# LSM6DSMTR.net
KiCad netlist of a schematic drawn in Altium Designer
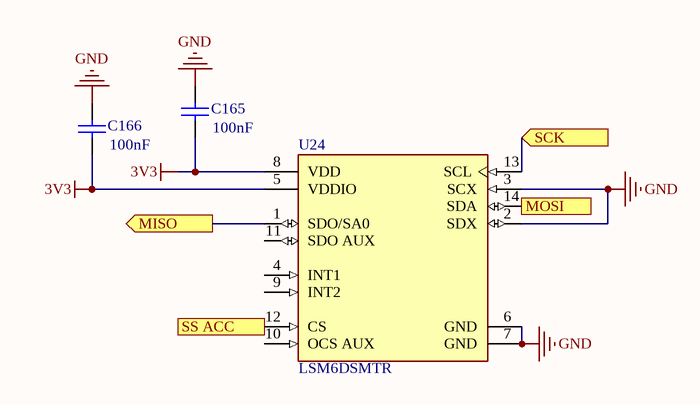
[diagram p0: LSM6DSMTR.SchDoc]

(export (version "E")
  (design (tool "Eeschema 10.0.6"))
  (components
    (comp (ref "C165")
      (value "100nF")
      (footprint "1608[0603]")
      (description "Capacitor")
      (fields (field (name "Comment") "Cap") (field (name "PUBLISHER") "Altium Limited"))
      (libsource (lib "Miscellaneous Devices") (part "Cap"))
    )
    (comp (ref "C166")
      (value "100nF")
      (footprint "1608[0603]")
      (description "Capacitor")
      (fields (field (name "Comment") "Cap") (field (name "PUBLISHER") "Altium Limited"))
      (libsource (lib "Miscellaneous Devices") (part "Cap"))
    )
    (comp (ref "U24")
      (value "LSM6DSMTR")
      (footprint "FP-LGA-14L-DM00249496-MFG")
      (description "IMU ACCEL/GYRO I2C/SPI 14LGA")
      (fields
        (field (name "OCTOPART") "https://octopart.com/lsm6dsmtr-stmicroelectronics-66358194")
        (field (name "MANUFACTURER") "STMicroelectronics")
      )
      (libsource (lib "Altium Content Vault") (part "dd82ae232bae541fa9c740d21cb9072"))
    )
  )
  (nets
    (net (code "1") (name "/MISO") (class "Default")
      (node (ref "U24") (pin "1") (pinfunction "SDO/SA0_1") (pintype "bidirectional"))
    )
    (net (code "2") (name "/MOSI") (class "Default")
      (node (ref "U24") (pin "14") (pinfunction "SDA_14") (pintype "bidirectional"))
    )
    (net (code "3") (name "/SCK") (class "Default")
      (node (ref "U24") (pin "13") (pinfunction "SCL_13") (pintype "input"))
    )
    (net (code "4") (name "/SS ACC") (class "Default")
      (node (ref "U24") (pin "12") (pinfunction "CS_12") (pintype "input"))
    )
    (net (code "5") (name "3V3") (class "Default")
      (node (ref "C165") (pin "2") (pinfunction "2_2") (pintype "passive"))
      (node (ref "C166") (pin "2") (pinfunction "2_2") (pintype "passive"))
      (node (ref "U24") (pin "5") (pinfunction "VDDIO_5") (pintype "power_in"))
      (node (ref "U24") (pin "8") (pinfunction "VDD_8") (pintype "power_in"))
    )
    (net (code "6") (name "GND") (class "Default")
      (node (ref "C165") (pin "1") (pinfunction "1_1") (pintype "passive"))
      (node (ref "C166") (pin "1") (pinfunction "1_1") (pintype "passive"))
      (node (ref "U24") (pin "2") (pinfunction "SDX_2") (pintype "bidirectional"))
      (node (ref "U24") (pin "3") (pinfunction "SCX_3") (pintype "input"))
      (node (ref "U24") (pin "6") (pinfunction "GND_6") (pintype "power_in"))
      (node (ref "U24") (pin "7") (pinfunction "GND_7") (pintype "power_in"))
    )
    (net (code "7") (name "unconnected-(U24-INT1-Pad4)") (class "Default")
      (node (ref "U24") (pin "4") (pinfunction "INT1_4") (pintype "input"))
    )
    (net (code "8") (name "unconnected-(U24-INT2-Pad9)") (class "Default")
      (node (ref "U24") (pin "9") (pinfunction "INT2_9") (pintype "input"))
    )
    (net (code "9") (name "unconnected-(U24-OCS_AUX-Pad10)") (class "Default")
      (node (ref "U24") (pin "10") (pinfunction "OCS_AUX_10") (pintype "input"))
    )
    (net (code "10") (name "unconnected-(U24-SDO_AUX-Pad11)") (class "Default")
      (node (ref "U24") (pin "11") (pinfunction "SDO_AUX_11") (pintype "bidirectional"))
    )
  )
)
